# MSW_V1.net
KiCad netlist of a schematic drawn in Altium Designer
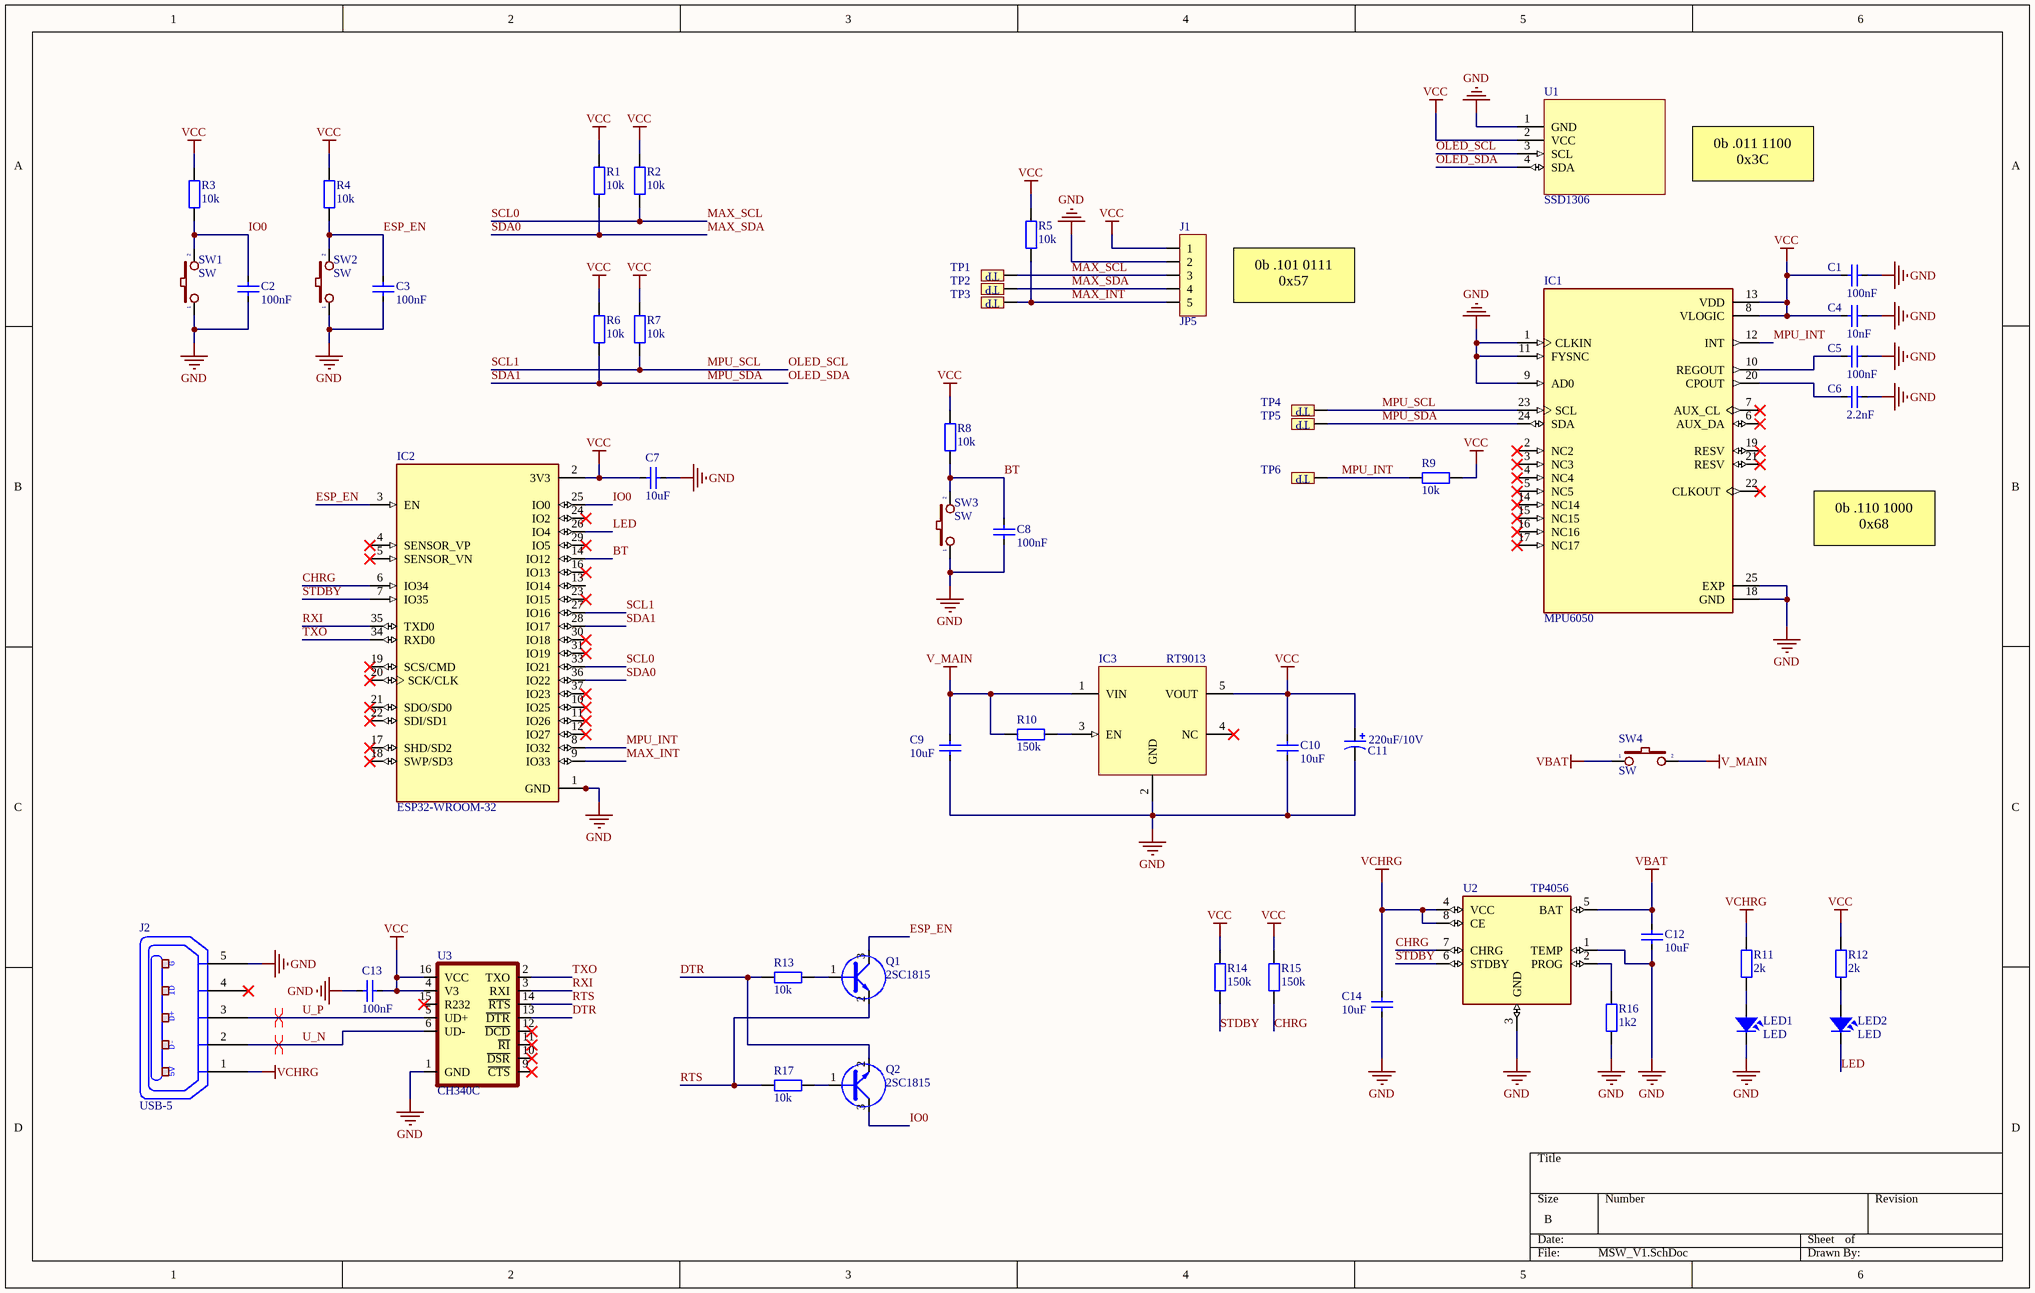
[diagram p0: MSW_V1.SchDoc]

(export (version "E")
  (design (tool "Eeschema 10.0.6"))
  (components
    (comp (ref "C1")
      (value "100nF")
      (footprint "CAP_0603")
      (description "Capacitor")
      (fields (field (name "PUBLISHER") "Altium Limited"))
      (libsource (lib "My Library") (part "CapSMD"))
    )
    (comp (ref "C2")
      (value "100nF")
      (footprint "CAP_0603")
      (description "Capacitor")
      (fields (field (name "PUBLISHER") "Altium Limited"))
      (libsource (lib "My Library") (part "CapSMD"))
    )
    (comp (ref "C3")
      (value "100nF")
      (footprint "CAP_0603")
      (description "Capacitor")
      (fields (field (name "PUBLISHER") "Altium Limited"))
      (libsource (lib "My Library") (part "CapSMD"))
    )
    (comp (ref "C4")
      (value "10nF")
      (footprint "CAP_0603")
      (description "Capacitor")
      (fields (field (name "PUBLISHER") "Altium Limited"))
      (libsource (lib "My Library") (part "CapSMD"))
    )
    (comp (ref "C5")
      (value "100nF")
      (footprint "CAP_0603")
      (description "Capacitor")
      (fields (field (name "PUBLISHER") "Altium Limited"))
      (libsource (lib "My Library") (part "CapSMD"))
    )
    (comp (ref "C6")
      (value "2.2nF")
      (footprint "CAP_0603")
      (description "Capacitor")
      (fields (field (name "PUBLISHER") "Altium Limited"))
      (libsource (lib "My Library") (part "CapSMD"))
    )
    (comp (ref "C7")
      (value "10uF")
      (footprint "CAP_0603")
      (description "Capacitor")
      (fields (field (name "PUBLISHER") "Altium Limited"))
      (libsource (lib "My Library") (part "CapSMD"))
    )
    (comp (ref "C8")
      (value "100nF")
      (footprint "CAP_0603")
      (description "Capacitor")
      (fields (field (name "PUBLISHER") "Altium Limited"))
      (libsource (lib "My Library") (part "CapSMD"))
    )
    (comp (ref "C9")
      (value "10uF")
      (footprint "CAP_0603")
      (description "Capacitor")
      (fields (field (name "PUBLISHER") "Altium Limited"))
      (libsource (lib "My Library") (part "CapSMD"))
    )
    (comp (ref "C10")
      (value "10uF")
      (footprint "CAP_0603")
      (description "Capacitor")
      (fields (field (name "PUBLISHER") "Altium Limited"))
      (libsource (lib "My Library") (part "CapSMD"))
    )
    (comp (ref "C11")
      (value "220uF/10V")
      (footprint "CAP_7343")
      (description "Polazied Tantalum Capacitor")
      (libsource (lib "My Library") (part "CAP_TAN_SMD"))
    )
    (comp (ref "C12")
      (value "10uF")
      (footprint "CAP_0603")
      (description "Capacitor")
      (fields (field (name "PUBLISHER") "Altium Limited"))
      (libsource (lib "My Library") (part "CapSMD"))
    )
    (comp (ref "C13")
      (value "100nF")
      (footprint "CAP_0603")
      (description "Capacitor")
      (fields (field (name "PUBLISHER") "Altium Limited"))
      (libsource (lib "My Library") (part "CapSMD"))
    )
    (comp (ref "C14")
      (value "10uF")
      (footprint "CAP_0603")
      (description "Capacitor")
      (fields (field (name "PUBLISHER") "Altium Limited"))
      (libsource (lib "My Library") (part "CapSMD"))
    )
    (comp (ref "IC1")
      (value "MPU6050")
      (footprint "QFN24")
      (description "3-axis gyroscope, 3-axis accelerometer")
      (libsource (lib "My Library") (part "MPU6050_Chip"))
    )
    (comp (ref "IC2")
      (value "ESP32-WROOM-32")
      (footprint "MODULE_ESP32-WROOM-32")
      (description "Bluetooth, WiFi Transceiver Module 2.4GHz ~ 2.5GHz Surface Mount")
      (fields (field (name "MF") "Espressif Systems") (field (name "DIGI-KEY_PART_NUMBER") "1904-1010-1-ND"))
      (libsource (lib "My Library") (part "ESP32-WROOM-32"))
    )
    (comp (ref "IC3")
      (value "RT9013")
      (footprint "SOT23-5")
      (description "RT9013-33GB IC REG LINEAR 3.3V 500mA SOT23-5")
      (libsource (lib "My Library") (part "RT9013"))
    )
    (comp (ref "J1")
      (value "JP5")
      (footprint "Header5 - TH - 1.25MM")
      (description "WR-PHD 2.54 mm Angled Socket Header")
      (fields
        (field (name "MANUFACTURER") "Würth Elektronik eiSos GmbH")
        (field (name "PARTNO") "613005143121")
        (field (name "CREATED BY") "Karrer Zheng")
      )
      (libsource (lib "My Library") (part "JP5x1"))
    )
    (comp (ref "J2")
      (value "USB-5")
      (footprint "USB-M1")
      (fields
        (field (name "MANUFACTURER") "FCI")
        (field (name "MANUFACTURER PART NUMBER") "10118193-0001LF")
        (field (name ".CREATOR") "MM")
        (field (name ".CHECKED PCB") "RF")
        (field (name ".CHECKED SCH") "MM")
      )
      (libsource (lib "My Library") (part "USB-5"))
    )
    (comp (ref "LED1")
      (value "LED")
      (footprint "LED-0805-Red")
      (description "LED Single colour Green and Red")
      (libsource (lib "My Library") (part "LED"))
    )
    (comp (ref "LED2")
      (value "LED")
      (footprint "LED-1206-Blue")
      (description "LED Single colour Green and Red")
      (libsource (lib "My Library") (part "LED"))
    )
    (comp (ref "Q1")
      (value "2SC1815")
      (footprint "SOT23D")
      (description "NPN 600mW, ECB")
      (libsource (lib "") (part "C1815_1"))
    )
    (comp (ref "Q2")
      (value "2SC1815")
      (footprint "SOT23D")
      (description "NPN 600mW, ECB")
      (libsource (lib "My Library") (part "C1815"))
    )
    (comp (ref "R1")
      (value "10k")
      (footprint "RES-SMD-0603")
      (description "Resistor SMD")
      (fields
        (field (name "MANUFACTURER") "Generic Components")
        (field (name "PUBLISHER") "Altium Hobart Technology Centre")
      )
      (libsource (lib "My Library") (part "Resistor - SMD"))
    )
    (comp (ref "R2")
      (value "10k")
      (footprint "RES-SMD-0603")
      (description "Resistor SMD")
      (fields
        (field (name "MANUFACTURER") "Generic Components")
        (field (name "PUBLISHER") "Altium Hobart Technology Centre")
      )
      (libsource (lib "My Library") (part "Resistor - SMD"))
    )
    (comp (ref "R3")
      (value "10k")
      (footprint "RES-SMD-0603")
      (description "Resistor SMD")
      (fields
        (field (name "MANUFACTURER") "Generic Components")
        (field (name "PUBLISHER") "Altium Hobart Technology Centre")
      )
      (libsource (lib "My Library") (part "Resistor - SMD"))
    )
    (comp (ref "R4")
      (value "10k")
      (footprint "RES-SMD-0603")
      (description "Resistor SMD")
      (fields
        (field (name "MANUFACTURER") "Generic Components")
        (field (name "PUBLISHER") "Altium Hobart Technology Centre")
      )
      (libsource (lib "My Library") (part "Resistor - SMD"))
    )
    (comp (ref "R5")
      (value "10k")
      (footprint "RES-SMD-0603")
      (description "Resistor SMD")
      (fields
        (field (name "MANUFACTURER") "Generic Components")
        (field (name "PUBLISHER") "Altium Hobart Technology Centre")
      )
      (libsource (lib "My Library") (part "Resistor - SMD"))
    )
    (comp (ref "R6")
      (value "10k")
      (footprint "RES-SMD-0603")
      (description "Resistor SMD")
      (fields
        (field (name "MANUFACTURER") "Generic Components")
        (field (name "PUBLISHER") "Altium Hobart Technology Centre")
      )
      (libsource (lib "My Library") (part "Resistor - SMD"))
    )
    (comp (ref "R7")
      (value "10k")
      (footprint "RES-SMD-0603")
      (description "Resistor SMD")
      (fields
        (field (name "MANUFACTURER") "Generic Components")
        (field (name "PUBLISHER") "Altium Hobart Technology Centre")
      )
      (libsource (lib "My Library") (part "Resistor - SMD"))
    )
    (comp (ref "R8")
      (value "10k")
      (footprint "RES-SMD-0603")
      (description "Resistor SMD")
      (fields
        (field (name "MANUFACTURER") "Generic Components")
        (field (name "PUBLISHER") "Altium Hobart Technology Centre")
      )
      (libsource (lib "My Library") (part "Resistor - SMD"))
    )
    (comp (ref "R9")
      (value "10k")
      (footprint "RES-SMD-0603")
      (description "Resistor SMD")
      (fields
        (field (name "MANUFACTURER") "Generic Components")
        (field (name "PUBLISHER") "Altium Hobart Technology Centre")
      )
      (libsource (lib "My Library") (part "Resistor - SMD"))
    )
    (comp (ref "R10")
      (value "150k")
      (footprint "RES-SMD-0603")
      (description "Resistor SMD")
      (fields
        (field (name "MANUFACTURER") "Generic Components")
        (field (name "PUBLISHER") "Altium Hobart Technology Centre")
      )
      (libsource (lib "My Library") (part "Resistor - SMD"))
    )
    (comp (ref "R11")
      (value "2k")
      (footprint "RES-SMD-0603")
      (description "Resistor SMD")
      (fields
        (field (name "MANUFACTURER") "Generic Components")
        (field (name "PUBLISHER") "Altium Hobart Technology Centre")
      )
      (libsource (lib "My Library") (part "Resistor - SMD"))
    )
    (comp (ref "R12")
      (value "2k")
      (footprint "RES-SMD-0603")
      (description "Resistor SMD")
      (fields
        (field (name "MANUFACTURER") "Generic Components")
        (field (name "PUBLISHER") "Altium Hobart Technology Centre")
      )
      (libsource (lib "My Library") (part "Resistor - SMD"))
    )
    (comp (ref "R13")
      (value "10k")
      (footprint "RES-SMD-0603")
      (description "Resistor SMD")
      (fields
        (field (name "MANUFACTURER") "Generic Components")
        (field (name "PUBLISHER") "Altium Hobart Technology Centre")
      )
      (libsource (lib "My Library") (part "Resistor - SMD"))
    )
    (comp (ref "R14")
      (value "150k")
      (footprint "RES-SMD-0603")
      (description "Resistor SMD")
      (fields
        (field (name "MANUFACTURER") "Generic Components")
        (field (name "PUBLISHER") "Altium Hobart Technology Centre")
      )
      (libsource (lib "My Library") (part "Resistor - SMD"))
    )
    (comp (ref "R15")
      (value "150k")
      (footprint "RES-SMD-0603")
      (description "Resistor SMD")
      (fields
        (field (name "MANUFACTURER") "Generic Components")
        (field (name "PUBLISHER") "Altium Hobart Technology Centre")
      )
      (libsource (lib "My Library") (part "Resistor - SMD"))
    )
    (comp (ref "R16")
      (value "1k2")
      (footprint "RES-SMD-0603")
      (description "Resistor SMD")
      (fields
        (field (name "MANUFACTURER") "Generic Components")
        (field (name "PUBLISHER") "Altium Hobart Technology Centre")
      )
      (libsource (lib "My Library") (part "Resistor - SMD"))
    )
    (comp (ref "R17")
      (value "10k")
      (footprint "RES-SMD-0603")
      (description "Resistor SMD")
      (fields
        (field (name "MANUFACTURER") "Generic Components")
        (field (name "PUBLISHER") "Altium Hobart Technology Centre")
      )
      (libsource (lib "My Library") (part "Resistor - SMD"))
    )
    (comp (ref "SW1")
      (value "SW")
      (footprint "SW 3x2x4")
      (description "Switch button 2 pin")
      (libsource (lib "My Library") (part "SW2"))
    )
    (comp (ref "SW2")
      (value "SW")
      (footprint "SW 3x2x4")
      (description "Switch button 2 pin")
      (libsource (lib "My Library") (part "SW2"))
    )
    (comp (ref "SW3")
      (value "SW")
      (footprint "SW 3x2x4")
      (description "Switch button 2 pin")
      (libsource (lib "My Library") (part "SW2"))
    )
    (comp (ref "SW4")
      (value "SW")
      (footprint "SW102_SIDE")
      (description "Switch button 2 pin")
      (libsource (lib "My Library") (part "SW2"))
    )
    (comp (ref "TP1")
      (value "TP")
      (footprint "TP_SMD")
      (description "CONNECT 1")
      (libsource (lib "My Library") (part "TP"))
    )
    (comp (ref "TP2")
      (value "TP")
      (footprint "TP_SMD")
      (description "CONNECT 1")
      (libsource (lib "My Library") (part "TP"))
    )
    (comp (ref "TP3")
      (value "TP")
      (footprint "TP_SMD")
      (description "CONNECT 1")
      (libsource (lib "My Library") (part "TP"))
    )
    (comp (ref "TP4")
      (value "TP")
      (footprint "TP_SMD")
      (description "CONNECT 1")
      (libsource (lib "My Library") (part "TP"))
    )
    (comp (ref "TP5")
      (value "TP")
      (footprint "TP_SMD")
      (description "CONNECT 1")
      (libsource (lib "My Library") (part "TP"))
    )
    (comp (ref "TP6")
      (value "TP")
      (footprint "TP_SMD")
      (description "CONNECT 1")
      (libsource (lib "My Library") (part "TP"))
    )
    (comp (ref "U1")
      (value "SSD1306")
      (footprint "OLED 1.3 SSD1306 PRETTY NON POLE")
      (description "OLED Display 1.3\" SSD1306")
      (libsource (lib "My Library") (part "OLED 1.3 SSD1306"))
    )
    (comp (ref "U2")
      (value "TP4056")
      (footprint "TP4056")
      (description "Complete single cell Li-Ion battery with a constant current / constant voltage linear charger")
      (libsource (lib "My Library") (part "TP4056"))
    )
    (comp (ref "U3")
      (value "CH340C")
      (footprint "SOP-16")
      (description "USB to serial chip CH340")
      (fields (field (name "MF") "WCH"))
      (libsource (lib "My Library") (part "CH340C"))
    )
  )
  (nets
    (net (code "1") (name "/BT") (class "Default")
      (node (ref "C8") (pin "1") (pinfunction "1_1") (pintype "passive"))
      (node (ref "IC2") (pin "14") (pinfunction "IO12_14") (pintype "bidirectional"))
      (node (ref "R8") (pin "1") (pinfunction "1_1") (pintype "passive"))
      (node (ref "SW3") (pin "2") (pinfunction "2_2") (pintype "passive"))
    )
    (net (code "2") (name "/CHRG") (class "Default")
      (node (ref "IC2") (pin "6") (pinfunction "IO34_6") (pintype "input"))
      (node (ref "R15") (pin "2") (pinfunction "2_2") (pintype "passive"))
      (node (ref "U2") (pin "7") (pinfunction "CHRG_7") (pintype "bidirectional"))
    )
    (net (code "3") (name "/DTR") (class "Default")
      (node (ref "Q2") (pin "2") (pinfunction "E_2") (pintype "passive"))
      (node (ref "R13") (pin "2") (pinfunction "2_2") (pintype "passive"))
      (node (ref "U3") (pin "13") (pinfunction "~{DTR}_13") (pintype "bidirectional"))
    )
    (net (code "4") (name "/ESP_EN") (class "Default")
      (node (ref "C3") (pin "1") (pinfunction "1_1") (pintype "passive"))
      (node (ref "IC2") (pin "3") (pinfunction "EN_3") (pintype "input"))
      (node (ref "Q1") (pin "3") (pinfunction "C_3") (pintype "passive"))
      (node (ref "R4") (pin "1") (pinfunction "1_1") (pintype "passive"))
      (node (ref "SW2") (pin "2") (pinfunction "2_2") (pintype "passive"))
    )
    (net (code "5") (name "/IO0") (class "Default")
      (node (ref "C2") (pin "1") (pinfunction "1_1") (pintype "passive"))
      (node (ref "IC2") (pin "25") (pinfunction "IO0_25") (pintype "bidirectional"))
      (node (ref "Q2") (pin "3") (pinfunction "C_3") (pintype "passive"))
      (node (ref "R3") (pin "1") (pinfunction "1_1") (pintype "passive"))
      (node (ref "SW1") (pin "2") (pinfunction "2_2") (pintype "passive"))
    )
    (net (code "6") (name "/LED") (class "Default")
      (node (ref "IC2") (pin "26") (pinfunction "IO4_26") (pintype "bidirectional"))
      (node (ref "LED2") (pin "2") (pinfunction "2_2") (pintype "passive"))
    )
    (net (code "7") (name "/MAX_INT") (class "Default")
      (node (ref "IC2") (pin "9") (pinfunction "IO33_9") (pintype "bidirectional"))
      (node (ref "J1") (pin "5") (pinfunction "5_5") (pintype "passive"))
      (node (ref "R5") (pin "2") (pinfunction "2_2") (pintype "passive"))
      (node (ref "TP3") (pin "1") (pinfunction "0_1") (pintype "passive"))
    )
    (net (code "8") (name "/MAX_SCL") (class "Default")
      (node (ref "IC2") (pin "33") (pinfunction "IO21_33") (pintype "bidirectional"))
      (node (ref "J1") (pin "3") (pinfunction "3_3") (pintype "passive"))
      (node (ref "R2") (pin "1") (pinfunction "1_1") (pintype "passive"))
      (node (ref "TP1") (pin "1") (pinfunction "0_1") (pintype "passive"))
    )
    (net (code "9") (name "/MAX_SDA") (class "Default")
      (node (ref "IC2") (pin "36") (pinfunction "IO22_36") (pintype "bidirectional"))
      (node (ref "J1") (pin "4") (pinfunction "4_4") (pintype "passive"))
      (node (ref "R1") (pin "1") (pinfunction "1_1") (pintype "passive"))
      (node (ref "TP2") (pin "1") (pinfunction "0_1") (pintype "passive"))
    )
    (net (code "10") (name "/MPU_INT") (class "Default")
      (node (ref "IC1") (pin "12") (pinfunction "INT_12") (pintype "output"))
      (node (ref "IC2") (pin "8") (pinfunction "IO32_8") (pintype "bidirectional"))
      (node (ref "R9") (pin "2") (pinfunction "2_2") (pintype "passive"))
      (node (ref "TP6") (pin "1") (pinfunction "0_1") (pintype "passive"))
    )
    (net (code "11") (name "/MPU_SCL") (class "Default")
      (node (ref "IC1") (pin "23") (pinfunction "SCL_23") (pintype "input"))
      (node (ref "IC2") (pin "27") (pinfunction "IO16_27") (pintype "bidirectional"))
      (node (ref "R7") (pin "1") (pinfunction "1_1") (pintype "passive"))
      (node (ref "TP4") (pin "1") (pinfunction "0_1") (pintype "passive"))
      (node (ref "U1") (pin "3") (pinfunction "SCL_3") (pintype "input"))
    )
    (net (code "12") (name "/MPU_SDA") (class "Default")
      (node (ref "IC1") (pin "24") (pinfunction "SDA_24") (pintype "bidirectional"))
      (node (ref "IC2") (pin "28") (pinfunction "IO17_28") (pintype "bidirectional"))
      (node (ref "R6") (pin "1") (pinfunction "1_1") (pintype "passive"))
      (node (ref "TP5") (pin "1") (pinfunction "0_1") (pintype "passive"))
      (node (ref "U1") (pin "4") (pinfunction "SDA_4") (pintype "bidirectional"))
    )
    (net (code "13") (name "/RTS") (class "Default")
      (node (ref "Q1") (pin "2") (pinfunction "E_2") (pintype "passive"))
      (node (ref "R17") (pin "2") (pinfunction "2_2") (pintype "passive"))
      (node (ref "U3") (pin "14") (pinfunction "~{RTS}_14") (pintype "bidirectional"))
    )
    (net (code "14") (name "/RXI") (class "Default")
      (node (ref "IC2") (pin "35") (pinfunction "TXD0_35") (pintype "bidirectional"))
      (node (ref "U3") (pin "3") (pinfunction "RXI_3") (pintype "bidirectional"))
    )
    (net (code "15") (name "/STDBY") (class "Default")
      (node (ref "IC2") (pin "7") (pinfunction "IO35_7") (pintype "input"))
      (node (ref "R14") (pin "2") (pinfunction "2_2") (pintype "passive"))
      (node (ref "U2") (pin "6") (pinfunction "STDBY_6") (pintype "bidirectional"))
    )
    (net (code "16") (name "/TXO") (class "Default")
      (node (ref "IC2") (pin "34") (pinfunction "RXD0_34") (pintype "bidirectional"))
      (node (ref "U3") (pin "2") (pinfunction "TXO_2") (pintype "bidirectional"))
    )
    (net (code "17") (name "/U_N") (class "Default")
      (node (ref "J2") (pin "2") (pinfunction "P2_2") (pintype "passive"))
      (node (ref "U3") (pin "6") (pinfunction "UD-_6") (pintype "bidirectional"))
    )
    (net (code "18") (name "/U_P") (class "Default")
      (node (ref "J2") (pin "3") (pinfunction "P3_3") (pintype "passive"))
      (node (ref "U3") (pin "5") (pinfunction "UD+_5") (pintype "bidirectional"))
    )
    (net (code "19") (name "GND") (class "Default")
      (node (ref "C1") (pin "1") (pinfunction "1_1") (pintype "passive"))
      (node (ref "C10") (pin "1") (pinfunction "1_1") (pintype "passive"))
      (node (ref "C11") (pin "2") (pinfunction "2_2") (pintype "passive"))
      (node (ref "C12") (pin "1") (pinfunction "1_1") (pintype "passive"))
      (node (ref "C13") (pin "1") (pinfunction "1_1") (pintype "passive"))
      (node (ref "C14") (pin "1") (pinfunction "1_1") (pintype "passive"))
      (node (ref "C2") (pin "2") (pinfunction "2_2") (pintype "passive"))
      (node (ref "C3") (pin "2") (pinfunction "2_2") (pintype "passive"))
      (node (ref "C4") (pin "1") (pinfunction "1_1") (pintype "passive"))
      (node (ref "C5") (pin "1") (pinfunction "1_1") (pintype "passive"))
      (node (ref "C6") (pin "1") (pinfunction "1_1") (pintype "passive"))
      (node (ref "C7") (pin "2") (pinfunction "2_2") (pintype "passive"))
      (node (ref "C8") (pin "2") (pinfunction "2_2") (pintype "passive"))
      (node (ref "C9") (pin "1") (pinfunction "1_1") (pintype "passive"))
      (node (ref "IC1") (pin "1") (pinfunction "CLKIN_1") (pintype "input"))
      (node (ref "IC1") (pin "11") (pinfunction "FYSNC_11") (pintype "input"))
      (node (ref "IC1") (pin "18") (pinfunction "GND_18") (pintype "power_in"))
      (node (ref "IC1") (pin "25") (pinfunction "EXP_25") (pintype "power_in"))
      (node (ref "IC1") (pin "9") (pinfunction "AD0_9") (pintype "input"))
      (node (ref "IC2") (pin "1") (pinfunction "GND_1") (pintype "power_in"))
      (node (ref "IC2") (pin "15") (pinfunction "GND_15") (pintype "power_in"))
      (node (ref "IC2") (pin "38") (pinfunction "GND_38") (pintype "power_in"))
      (node (ref "IC2") (pin "39_1") (pinfunction "GND_39_1") (pintype "power_in"))
      (node (ref "IC2") (pin "39_10") (pinfunction "GND_39_10") (pintype "power_in"))
      (node (ref "IC2") (pin "39_11") (pinfunction "GND_39_11") (pintype "power_in"))
      (node (ref "IC2") (pin "39_12") (pinfunction "GND_39_12") (pintype "power_in"))
      (node (ref "IC2") (pin "39_13") (pinfunction "GND_39_13") (pintype "power_in"))
      (node (ref "IC2") (pin "39_14") (pinfunction "GND_39_14") (pintype "power_in"))
      (node (ref "IC2") (pin "39_15") (pinfunction "GND_39_15") (pintype "power_in"))
      (node (ref "IC2") (pin "39_16") (pinfunction "GND_39_16") (pintype "power_in"))
      (node (ref "IC2") (pin "39_17") (pinfunction "GND_39_17") (pintype "power_in"))
      (node (ref "IC2") (pin "39_18") (pinfunction "GND_39_18") (pintype "power_in"))
      (node (ref "IC2") (pin "39_19") (pinfunction "GND_39_19") (pintype "power_in"))
      (node (ref "IC2") (pin "39_2") (pinfunction "GND_39_2") (pintype "power_in"))
      (node (ref "IC2") (pin "39_20") (pinfunction "GND_39_20") (pintype "power_in"))
      (node (ref "IC2") (pin "39_21") (pinfunction "GND_39_21") (pintype "power_in"))
      (node (ref "IC2") (pin "39_3") (pinfunction "GND_39_3") (pintype "power_in"))
      (node (ref "IC2") (pin "39_4") (pinfunction "GND_39_4") (pintype "power_in"))
      (node (ref "IC2") (pin "39_5") (pinfunction "GND_39_5") (pintype "power_in"))
      (node (ref "IC2") (pin "39_6") (pinfunction "GND_39_6") (pintype "power_in"))
      (node (ref "IC2") (pin "39_7") (pinfunction "GND_39_7") (pintype "power_in"))
      (node (ref "IC2") (pin "39_8") (pinfunction "GND_39_8") (pintype "power_in"))
      (node (ref "IC2") (pin "39_9") (pinfunction "GND_39_9") (pintype "power_in"))
      (node (ref "IC3") (pin "2") (pinfunction "GND_2") (pintype "power_in"))
      (node (ref "J1") (pin "2") (pinfunction "2_2") (pintype "passive"))
      (node (ref "J2") (pin "5") (pinfunction "P5_5") (pintype "passive"))
      (node (ref "LED1") (pin "2") (pinfunction "2_2") (pintype "passive"))
      (node (ref "R16") (pin "1") (pinfunction "1_1") (pintype "passive"))
      (node (ref "SW1") (pin "1") (pinfunction "1_1") (pintype "passive"))
      (node (ref "SW2") (pin "1") (pinfunction "1_1") (pintype "passive"))
      (node (ref "SW3") (pin "1") (pinfunction "1_1") (pintype "passive"))
      (node (ref "U1") (pin "1") (pinfunction "GND_1") (pintype "power_in"))
      (node (ref "U2") (pin "1") (pinfunction "TEMP_1") (pintype "bidirectional"))
      (node (ref "U2") (pin "3") (pinfunction "GND_3") (pintype "bidirectional"))
      (node (ref "U3") (pin "1") (pinfunction "GND_1") (pintype "bidirectional"))
    )
    (net (code "20") (name "Net-(IC1-CPOUT)") (class "Default")
      (node (ref "C6") (pin "2") (pinfunction "2_2") (pintype "passive"))
      (node (ref "IC1") (pin "20") (pinfunction "CPOUT_20") (pintype "output"))
    )
    (net (code "21") (name "Net-(IC1-REGOUT)") (class "Default")
      (node (ref "C5") (pin "2") (pinfunction "2_2") (pintype "passive"))
      (node (ref "IC1") (pin "10") (pinfunction "REGOUT_10") (pintype "output"))
    )
    (net (code "22") (name "Net-(IC3-EN)") (class "Default")
      (node (ref "IC3") (pin "3") (pinfunction "EN_3") (pintype "input"))
      (node (ref "R10") (pin "2") (pinfunction "2_2") (pintype "passive"))
    )
    (net (code "23") (name "Net-(LED1-Pad1)") (class "Default")
      (node (ref "LED1") (pin "1") (pinfunction "1_1") (pintype "passive"))
      (node (ref "R11") (pin "1") (pinfunction "1_1") (pintype "passive"))
    )
    (net (code "24") (name "Net-(LED2-Pad1)") (class "Default")
      (node (ref "LED2") (pin "1") (pinfunction "1_1") (pintype "passive"))
      (node (ref "R12") (pin "1") (pinfunction "1_1") (pintype "passive"))
    )
    (net (code "25") (name "Net-(Q1-B)") (class "Default")
      (node (ref "Q1") (pin "1") (pinfunction "B_1") (pintype "passive"))
      (node (ref "R13") (pin "1") (pinfunction "1_1") (pintype "passive"))
    )
    (net (code "26") (name "Net-(Q2-B)") (class "Default")
      (node (ref "Q2") (pin "1") (pinfunction "B_1") (pintype "passive"))
      (node (ref "R17") (pin "1") (pinfunction "1_1") (pintype "passive"))
    )
    (net (code "27") (name "Net-(U2-PROG)") (class "Default")
      (node (ref "R16") (pin "2") (pinfunction "2_2") (pintype "passive"))
      (node (ref "U2") (pin "2") (pinfunction "PROG_2") (pintype "bidirectional"))
    )
    (net (code "28") (name "VBAT") (class "Default")
      (node (ref "C12") (pin "2") (pinfunction "2_2") (pintype "passive"))
      (node (ref "SW4") (pin "1") (pinfunction "1_1") (pintype "passive"))
      (node (ref "U2") (pin "5") (pinfunction "BAT_5") (pintype "bidirectional"))
    )
    (net (code "29") (name "VCC") (class "Default")
      (node (ref "C1") (pin "2") (pinfunction "2_2") (pintype "passive"))
      (node (ref "C10") (pin "2") (pinfunction "2_2") (pintype "passive"))
      (node (ref "C11") (pin "1") (pinfunction "1_1") (pintype "passive"))
      (node (ref "C13") (pin "2") (pinfunction "2_2") (pintype "passive"))
      (node (ref "C4") (pin "2") (pinfunction "2_2") (pintype "passive"))
      (node (ref "C7") (pin "1") (pinfunction "1_1") (pintype "passive"))
      (node (ref "IC1") (pin "13") (pinfunction "VDD_13") (pintype "power_in"))
      (node (ref "IC1") (pin "8") (pinfunction "VLOGIC_8") (pintype "power_in"))
      (node (ref "IC2") (pin "2") (pinfunction "3V3_2") (pintype "power_in"))
      (node (ref "IC3") (pin "5") (pinfunction "VOUT_5") (pintype "power_in"))
      (node (ref "J1") (pin "1") (pinfunction "1_1") (pintype "passive"))
      (node (ref "R1") (pin "2") (pinfunction "2_2") (pintype "passive"))
      (node (ref "R12") (pin "2") (pinfunction "2_2") (pintype "passive"))
      (node (ref "R14") (pin "1") (pinfunction "1_1") (pintype "passive"))
      (node (ref "R15") (pin "1") (pinfunction "1_1") (pintype "passive"))
      (node (ref "R2") (pin "2") (pinfunction "2_2") (pintype "passive"))
      (node (ref "R3") (pin "2") (pinfunction "2_2") (pintype "passive"))
      (node (ref "R4") (pin "2") (pinfunction "2_2") (pintype "passive"))
      (node (ref "R5") (pin "1") (pinfunction "1_1") (pintype "passive"))
      (node (ref "R6") (pin "2") (pinfunction "2_2") (pintype "passive"))
      (node (ref "R7") (pin "2") (pinfunction "2_2") (pintype "passive"))
      (node (ref "R8") (pin "2") (pinfunction "2_2") (pintype "passive"))
      (node (ref "R9") (pin "1") (pinfunction "1_1") (pintype "passive"))
      (node (ref "U1") (pin "2") (pinfunction "VCC_2") (pintype "power_in"))
      (node (ref "U3") (pin "16") (pinfunction "VCC_16") (pintype "bidirectional"))
      (node (ref "U3") (pin "4") (pinfunction "V3_4") (pintype "bidirectional"))
    )
    (net (code "30") (name "VCHRG") (class "Default")
      (node (ref "C14") (pin "2") (pinfunction "2_2") (pintype "passive"))
      (node (ref "J2") (pin "1") (pinfunction "P1_1") (pintype "passive"))
      (node (ref "R11") (pin "2") (pinfunction "2_2") (pintype "passive"))
      (node (ref "U2") (pin "4") (pinfunction "VCC_4") (pintype "bidirectional"))
      (node (ref "U2") (pin "8") (pinfunction "CE_8") (pintype "bidirectional"))
    )
    (net (code "31") (name "V_MAIN") (class "Default")
      (node (ref "C9") (pin "2") (pinfunction "2_2") (pintype "passive"))
      (node (ref "IC3") (pin "1") (pinfunction "VIN_1") (pintype "power_in"))
      (node (ref "R10") (pin "1") (pinfunction "1_1") (pintype "passive"))
      (node (ref "SW4") (pin "2") (pinfunction "2_2") (pintype "passive"))
    )
    (net (code "32") (name "unconnected-(IC1-AUX_CL-Pad7)") (class "Default")
      (node (ref "IC1") (pin "7") (pinfunction "AUX_CL_7") (pintype "output+no_connect"))
    )
    (net (code "33") (name "unconnected-(IC1-AUX_DA-Pad6)") (class "Default")
      (node (ref "IC1") (pin "6") (pinfunction "AUX_DA_6") (pintype "bidirectional+no_connect"))
    )
    (net (code "34") (name "unconnected-(IC1-CLKOUT-Pad22)") (class "Default")
      (node (ref "IC1") (pin "22") (pinfunction "CLKOUT_22") (pintype "output+no_connect"))
    )
    (net (code "35") (name "unconnected-(IC1-NC2-Pad2)") (class "Default")
      (node (ref "IC1") (pin "2") (pinfunction "NC2_2") (pintype "input+no_connect"))
    )
    (net (code "36") (name "unconnected-(IC1-NC3-Pad3)") (class "Default")
      (node (ref "IC1") (pin "3") (pinfunction "NC3_3") (pintype "input+no_connect"))
    )
    (net (code "37") (name "unconnected-(IC1-NC4-Pad4)") (class "Default")
      (node (ref "IC1") (pin "4") (pinfunction "NC4_4") (pintype "input+no_connect"))
    )
    (net (code "38") (name "unconnected-(IC1-NC5-Pad5)") (class "Default")
      (node (ref "IC1") (pin "5") (pinfunction "NC5_5") (pintype "input+no_connect"))
    )
    (net (code "39") (name "unconnected-(IC1-NC14-Pad14)") (class "Default")
      (node (ref "IC1") (pin "14") (pinfunction "NC14_14") (pintype "input+no_connect"))
    )
    (net (code "40") (name "unconnected-(IC1-NC15-Pad15)") (class "Default")
      (node (ref "IC1") (pin "15") (pinfunction "NC15_15") (pintype "input+no_connect"))
    )
    (net (code "41") (name "unconnected-(IC1-NC16-Pad16)") (class "Default")
      (node (ref "IC1") (pin "16") (pinfunction "NC16_16") (pintype "input+no_connect"))
    )
    (net (code "42") (name "unconnected-(IC1-NC17-Pad17)") (class "Default")
      (node (ref "IC1") (pin "17") (pinfunction "NC17_17") (pintype "input+no_connect"))
    )
    (net (code "43") (name "unconnected-(IC1-RESV-Pad19)") (class "Default")
      (node (ref "IC1") (pin "19") (pinfunction "RESV_19") (pintype "bidirectional+no_connect"))
    )
    (net (code "44") (name "unconnected-(IC1-RESV-Pad21)") (class "Default")
      (node (ref "IC1") (pin "21") (pinfunction "RESV_21") (pintype "bidirectional+no_connect"))
    )
    (net (code "45") (name "unconnected-(IC2-IO2-Pad24)") (class "Default")
      (node (ref "IC2") (pin "24") (pinfunction "IO2_24") (pintype "bidirectional+no_connect"))
    )
    (net (code "46") (name "unconnected-(IC2-IO5-Pad29)") (class "Default")
      (node (ref "IC2") (pin "29") (pinfunction "IO5_29") (pintype "bidirectional+no_connect"))
    )
    (net (code "47") (name "unconnected-(IC2-IO13-Pad16)") (class "Default")
      (node (ref "IC2") (pin "16") (pinfunction "IO13_16") (pintype "bidirectional+no_connect"))
    )
    (net (code "48") (name "unconnected-(IC2-IO14-Pad13)") (class "Default")
      (node (ref "IC2") (pin "13") (pinfunction "IO14_13") (pintype "bidirectional"))
    )
    (net (code "49") (name "unconnected-(IC2-IO15-Pad23)") (class "Default")
      (node (ref "IC2") (pin "23") (pinfunction "IO15_23") (pintype "bidirectional+no_connect"))
    )
    (net (code "50") (name "unconnected-(IC2-IO18-Pad30)") (class "Default")
      (node (ref "IC2") (pin "30") (pinfunction "IO18_30") (pintype "bidirectional+no_connect"))
    )
    (net (code "51") (name "unconnected-(IC2-IO19-Pad31)") (class "Default")
      (node (ref "IC2") (pin "31") (pinfunction "IO19_31") (pintype "bidirectional+no_connect"))
    )
    (net (code "52") (name "unconnected-(IC2-IO23-Pad37)") (class "Default")
      (node (ref "IC2") (pin "37") (pinfunction "IO23_37") (pintype "bidirectional+no_connect"))
    )
    (net (code "53") (name "unconnected-(IC2-IO25-Pad10)") (class "Default")
      (node (ref "IC2") (pin "10") (pinfunction "IO25_10") (pintype "bidirectional+no_connect"))
    )
    (net (code "54") (name "unconnected-(IC2-IO26-Pad11)") (class "Default")
      (node (ref "IC2") (pin "11") (pinfunction "IO26_11") (pintype "bidirectional+no_connect"))
    )
    (net (code "55") (name "unconnected-(IC2-IO27-Pad12)") (class "Default")
      (node (ref "IC2") (pin "12") (pinfunction "IO27_12") (pintype "bidirectional+no_connect"))
    )
    (net (code "56") (name "unconnected-(IC2-SCK{slash}CLK-Pad20)") (class "Default")
      (node (ref "IC2") (pin "20") (pinfunction "SCK/CLK_20") (pintype "bidirectional+no_connect"))
    )
    (net (code "57") (name "unconnected-(IC2-SCS{slash}CMD-Pad19)") (class "Default")
      (node (ref "IC2") (pin "19") (pinfunction "SCS/CMD_19") (pintype "bidirectional+no_connect"))
    )
    (net (code "58") (name "unconnected-(IC2-SDI{slash}SD1-Pad22)") (class "Default")
      (node (ref "IC2") (pin "22") (pinfunction "SDI/SD1_22") (pintype "bidirectional+no_connect"))
    )
    (net (code "59") (name "unconnected-(IC2-SDO{slash}SD0-Pad21)") (class "Default")
      (node (ref "IC2") (pin "21") (pinfunction "SDO/SD0_21") (pintype "bidirectional+no_connect"))
    )
    (net (code "60") (name "unconnected-(IC2-SENSOR_VN-Pad5)") (class "Default")
      (node (ref "IC2") (pin "5") (pinfunction "SENSOR_VN_5") (pintype "input+no_connect"))
    )
    (net (code "61") (name "unconnected-(IC2-SENSOR_VP-Pad4)") (class "Default")
      (node (ref "IC2") (pin "4") (pinfunction "SENSOR_VP_4") (pintype "input+no_connect"))
    )
    (net (code "62") (name "unconnected-(IC2-SHD{slash}SD2-Pad17)") (class "Default")
      (node (ref "IC2") (pin "17") (pinfunction "SHD/SD2_17") (pintype "bidirectional+no_connect"))
    )
    (net (code "63") (name "unconnected-(IC2-SWP{slash}SD3-Pad18)") (class "Default")
      (node (ref "IC2") (pin "18") (pinfunction "SWP/SD3_18") (pintype "bidirectional+no_connect"))
    )
    (net (code "64") (name "unconnected-(IC3-NC-Pad4)") (class "Default")
      (node (ref "IC3") (pin "4") (pinfunction "NC_4") (pintype "passive+no_connect"))
    )
    (net (code "65") (name "unconnected-(J2-P4-Pad4)") (class "Default")
      (node (ref "J2") (pin "4") (pinfunction "P4_4") (pintype "passive+no_connect"))
    )
    (net (code "66") (name "unconnected-(U3-R232-Pad15)") (class "Default")
      (node (ref "U3") (pin "15") (pinfunction "R232_15") (pintype "bidirectional+no_connect"))
    )
    (net (code "67") (name "unconnected-(U3-~{CTS}-Pad9)") (class "Default")
      (node (ref "U3") (pin "9") (pinfunction "~{CTS}_9") (pintype "bidirectional+no_connect"))
    )
    (net (code "68") (name "unconnected-(U3-~{DCD}-Pad12)") (class "Default")
      (node (ref "U3") (pin "12") (pinfunction "~{DCD}_12") (pintype "bidirectional+no_connect"))
    )
    (net (code "69") (name "unconnected-(U3-~{DSR}-Pad10)") (class "Default")
      (node (ref "U3") (pin "10") (pinfunction "~{DSR}_10") (pintype "bidirectional+no_connect"))
    )
    (net (code "70") (name "unconnected-(U3-~{RI}-Pad11)") (class "Default")
      (node (ref "U3") (pin "11") (pinfunction "~{RI}_11") (pintype "bidirectional+no_connect"))
    )
  )
)
